# FTDI_Interface.net
KiCad netlist of a schematic drawn in Altium Designer
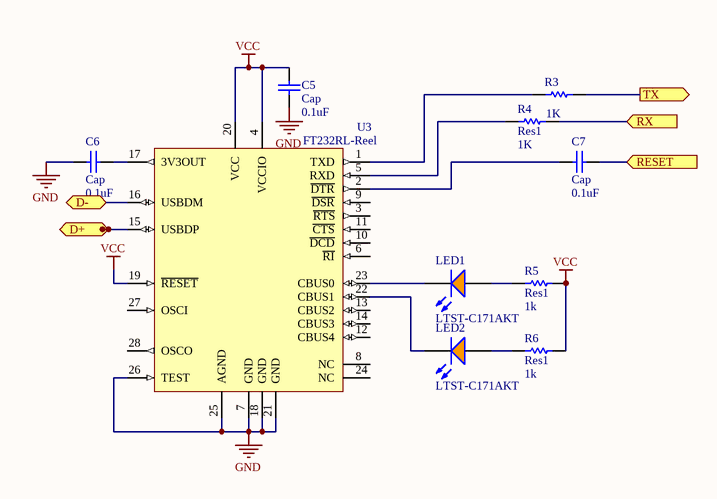
[diagram p0: FTDI_Interface.SchDoc]

(export (version "E")
  (design (tool "Eeschema 10.0.6"))
  (components
    (comp (ref "C5")
      (value "Cap")
      (footprint "C0805")
      (description "Capacitor")
      (fields (field (name "ALTIUM_VALUE") "0.1uF") (field (name "PUBLISHER") "Altium Limited"))
      (libsource (lib "Miscellaneous Devices") (part "Cap"))
    )
    (comp (ref "C6")
      (value "Cap")
      (footprint "C0805")
      (description "Capacitor")
      (fields (field (name "ALTIUM_VALUE") "0.1uF") (field (name "PUBLISHER") "Altium Limited"))
      (libsource (lib "Miscellaneous Devices") (part "Cap"))
    )
    (comp (ref "C7")
      (value "Cap")
      (footprint "C0805")
      (description "Capacitor")
      (fields (field (name "ALTIUM_VALUE") "0.1uF") (field (name "PUBLISHER") "Altium Limited"))
      (libsource (lib "Miscellaneous Devices") (part "Cap"))
    )
    (comp (ref "LED1")
      (value "LTST-C171AKT")
      (footprint "LTST-C171AKT_V")
      (description "LED Uni-Color Orange, 100 mW, 120 mA, -55 to 85 degC, 2-Pin SMD, RoHS, Tape and Reel")
      (fields (field (name "MANUFACTURER") "Lite-On"))
      (libsource (lib "Altium Content Vault") (part "CMP-1674-00004-5"))
    )
    (comp (ref "LED2")
      (value "LTST-C171AKT")
      (footprint "LTST-C171AKT_V")
      (description "LED Uni-Color Orange, 100 mW, 120 mA, -55 to 85 degC, 2-Pin SMD, RoHS, Tape and Reel")
      (fields (field (name "MANUFACTURER") "Lite-On"))
      (libsource (lib "Altium Content Vault") (part "CMP-1674-00004-5"))
    )
    (comp (ref "R3")
      (value "1K")
      (footprint "6-0805_L")
      (description "Resistor")
      (fields (field (name "Comment") "Res1") (field (name "PUBLISHER") "Altium Limited"))
      (libsource (lib "Miscellaneous Devices") (part "Res1"))
    )
    (comp (ref "R4")
      (value "Res1")
      (footprint "6-0805_L")
      (description "Resistor")
      (fields (field (name "ALTIUM_VALUE") "1K") (field (name "PUBLISHER") "Altium Limited"))
      (libsource (lib "Miscellaneous Devices") (part "Res1"))
    )
    (comp (ref "R5")
      (value "Res1")
      (footprint "6-0805_L")
      (description "Resistor")
      (fields (field (name "ALTIUM_VALUE") "1k") (field (name "PUBLISHER") "Altium Limited"))
      (libsource (lib "Miscellaneous Devices") (part "Res1"))
    )
    (comp (ref "R6")
      (value "Res1")
      (footprint "6-0805_L")
      (description "Resistor")
      (fields (field (name "ALTIUM_VALUE") "1k") (field (name "PUBLISHER") "Altium Limited"))
      (libsource (lib "Miscellaneous Devices") (part "Res1"))
    )
    (comp (ref "U3")
      (value "FT232RL-Reel")
      (footprint "SSOP-28_L")
      (description "USB UART Asynchronous Serial Data Transfer Chip, 28-pin SSOP, Tape and Reel")
      (fields (field (name "MANUFACTURER") "FTDI"))
      (libsource (lib "Altium Content Vault") (part "COM-UART-FT232R-IL28"))
    )
  )
  (nets
    (net (code "1") (name "/D+") (class "Default")
      (node (ref "U3") (pin "15") (pinfunction "USBDP_15") (pintype "bidirectional"))
    )
    (net (code "2") (name "/D-") (class "Default")
      (node (ref "U3") (pin "16") (pinfunction "USBDM_16") (pintype "bidirectional"))
    )
    (net (code "3") (name "/RESET") (class "Default")
      (node (ref "C7") (pin "1") (pinfunction "1_1") (pintype "passive"))
    )
    (net (code "4") (name "/RX") (class "Default")
      (node (ref "R4") (pin "2") (pinfunction "2_2") (pintype "passive"))
    )
    (net (code "5") (name "/TX") (class "Default")
      (node (ref "R3") (pin "2") (pinfunction "2_2") (pintype "passive"))
    )
    (net (code "6") (name "GND") (class "Default")
      (node (ref "C5") (pin "1") (pinfunction "1_1") (pintype "passive"))
      (node (ref "C6") (pin "1") (pinfunction "1_1") (pintype "passive"))
      (node (ref "U3") (pin "18") (pinfunction "GND_18") (pintype "power_in"))
      (node (ref "U3") (pin "21") (pinfunction "GND_21") (pintype "power_in"))
      (node (ref "U3") (pin "25") (pinfunction "AGND_25") (pintype "power_in"))
      (node (ref "U3") (pin "26") (pinfunction "TEST_26") (pintype "input"))
      (node (ref "U3") (pin "7") (pinfunction "GND_7") (pintype "power_in"))
    )
    (net (code "7") (name "Net-(LED1-A)") (class "Default")
      (node (ref "LED1") (pin "1") (pinfunction "A_1") (pintype "passive"))
      (node (ref "R5") (pin "1") (pinfunction "1_1") (pintype "passive"))
    )
    (net (code "8") (name "Net-(LED1-K)") (class "Default")
      (node (ref "LED1") (pin "2") (pinfunction "K_2") (pintype "passive"))
      (node (ref "U3") (pin "23") (pinfunction "CBUS0_23") (pintype "bidirectional"))
    )
    (net (code "9") (name "Net-(LED2-A)") (class "Default")
      (node (ref "LED2") (pin "1") (pinfunction "A_1") (pintype "passive"))
      (node (ref "R6") (pin "1") (pinfunction "1_1") (pintype "passive"))
    )
    (net (code "10") (name "Net-(LED2-K)") (class "Default")
      (node (ref "LED2") (pin "2") (pinfunction "K_2") (pintype "passive"))
      (node (ref "U3") (pin "22") (pinfunction "CBUS1_22") (pintype "bidirectional"))
    )
    (net (code "11") (name "Net-(U3-3V3OUT)") (class "Default")
      (node (ref "C6") (pin "2") (pinfunction "2_2") (pintype "passive"))
      (node (ref "U3") (pin "17") (pinfunction "3V3OUT_17") (pintype "output"))
    )
    (net (code "12") (name "Net-(U3-RXD)") (class "Default")
      (node (ref "R4") (pin "1") (pinfunction "1_1") (pintype "passive"))
      (node (ref "U3") (pin "5") (pinfunction "RXD_5") (pintype "input"))
    )
    (net (code "13") (name "Net-(U3-TXD)") (class "Default")
      (node (ref "R3") (pin "1") (pinfunction "1_1") (pintype "passive"))
      (node (ref "U3") (pin "1") (pinfunction "TXD_1") (pintype "output"))
    )
    (net (code "14") (name "Net-(U3-~{DTR})") (class "Default")
      (node (ref "C7") (pin "2") (pinfunction "2_2") (pintype "passive"))
      (node (ref "U3") (pin "2") (pinfunction "~{DTR}_2") (pintype "output"))
    )
    (net (code "15") (name "VCC") (class "Default")
      (node (ref "C5") (pin "2") (pinfunction "2_2") (pintype "passive"))
      (node (ref "R5") (pin "2") (pinfunction "2_2") (pintype "passive"))
      (node (ref "R6") (pin "2") (pinfunction "2_2") (pintype "passive"))
      (node (ref "U3") (pin "19") (pinfunction "~{RESET}_19") (pintype "input"))
      (node (ref "U3") (pin "20") (pinfunction "VCC_20") (pintype "power_in"))
      (node (ref "U3") (pin "4") (pinfunction "VCCIO_4") (pintype "power_in"))
    )
    (net (code "16") (name "unconnected-(U3-CBUS2-Pad13)") (class "Default")
      (node (ref "U3") (pin "13") (pinfunction "CBUS2_13") (pintype "bidirectional"))
    )
    (net (code "17") (name "unconnected-(U3-CBUS3-Pad14)") (class "Default")
      (node (ref "U3") (pin "14") (pinfunction "CBUS3_14") (pintype "bidirectional"))
    )
    (net (code "18") (name "unconnected-(U3-CBUS4-Pad12)") (class "Default")
      (node (ref "U3") (pin "12") (pinfunction "CBUS4_12") (pintype "bidirectional"))
    )
    (net (code "19") (name "unconnected-(U3-NC-Pad8)") (class "Default")
      (node (ref "U3") (pin "8") (pinfunction "NC_8") (pintype "passive"))
    )
    (net (code "20") (name "unconnected-(U3-NC-Pad24)") (class "Default")
      (node (ref "U3") (pin "24") (pinfunction "NC_24") (pintype "passive"))
    )
    (net (code "21") (name "unconnected-(U3-OSCI-Pad27)") (class "Default")
      (node (ref "U3") (pin "27") (pinfunction "OSCI_27") (pintype "input"))
    )
    (net (code "22") (name "unconnected-(U3-OSCO-Pad28)") (class "Default")
      (node (ref "U3") (pin "28") (pinfunction "OSCO_28") (pintype "output"))
    )
    (net (code "23") (name "unconnected-(U3-~{CTS}-Pad11)") (class "Default")
      (node (ref "U3") (pin "11") (pinfunction "~{CTS}_11") (pintype "input"))
    )
    (net (code "24") (name "unconnected-(U3-~{DCD}-Pad10)") (class "Default")
      (node (ref "U3") (pin "10") (pinfunction "~{DCD}_10") (pintype "input"))
    )
    (net (code "25") (name "unconnected-(U3-~{DSR}-Pad9)") (class "Default")
      (node (ref "U3") (pin "9") (pinfunction "~{DSR}_9") (pintype "input"))
    )
    (net (code "26") (name "unconnected-(U3-~{RI}-Pad6)") (class "Default")
      (node (ref "U3") (pin "6") (pinfunction "~{RI}_6") (pintype "input"))
    )
    (net (code "27") (name "unconnected-(U3-~{RTS}-Pad3)") (class "Default")
      (node (ref "U3") (pin "3") (pinfunction "~{RTS}_3") (pintype "output"))
    )
  )
)
